# PogoFTDI.net
KiCad netlist of a schematic drawn in EAGLE
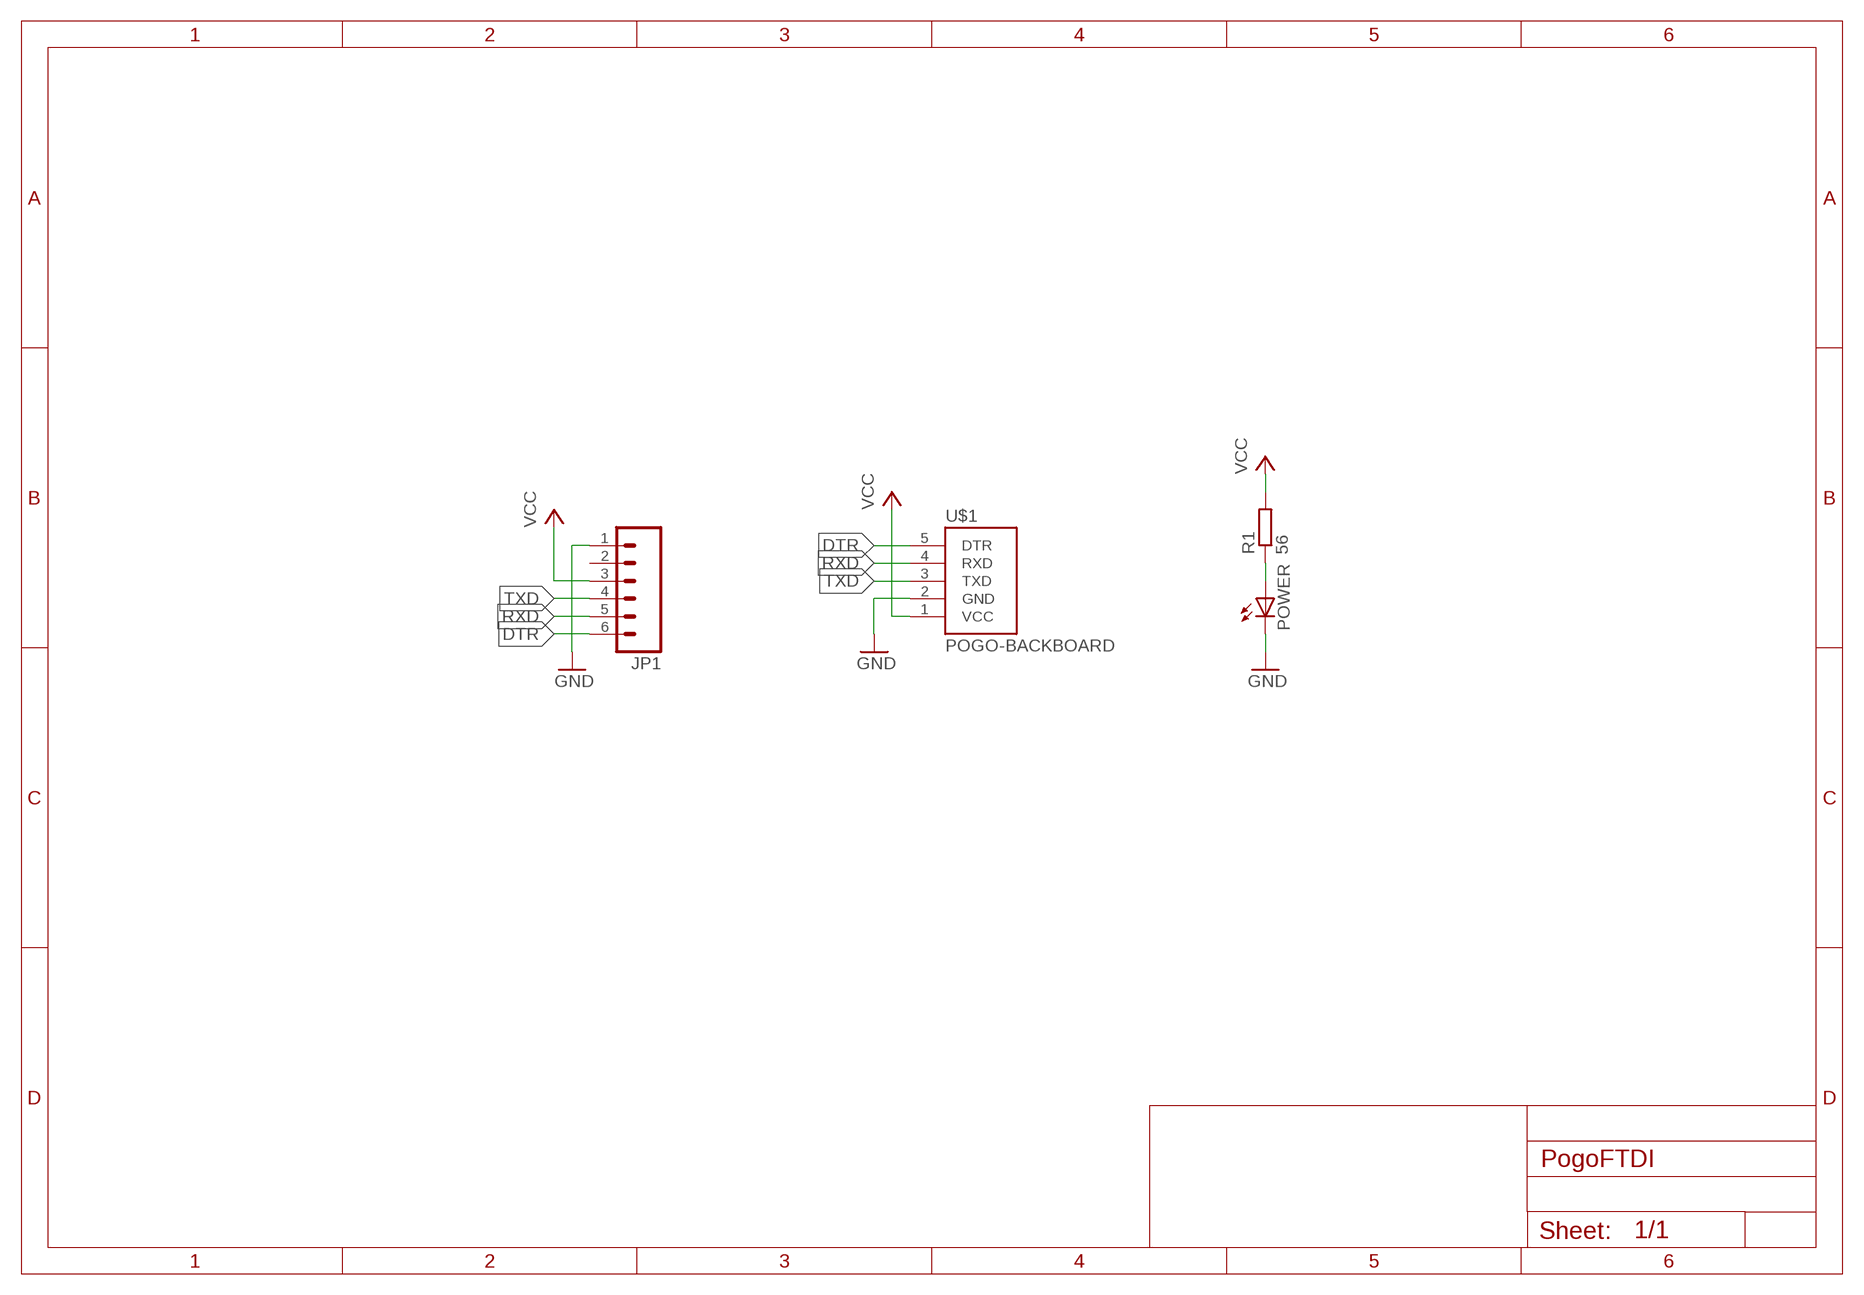
[diagram p0: schematic, sheet 1]

(export (version "E")
  (design (tool "Eeschema 10.0.6"))
  (components
    (comp (ref "JP1")
      (value "M06SIP")
      (footprint "eagle-import:1X06")
      (libsource (lib "eagle-import") (part "M06SIP"))
    )
    (comp (ref "POWER")
      (value "LEDCHIPLED_0603")
      (footprint "eagle-import:CHIPLED_0603")
      (libsource (lib "eagle-import") (part "LEDCHIPLED_0603"))
    )
    (comp (ref "R1")
      (value "56")
      (footprint "eagle-import:R0603")
      (libsource (lib "eagle-import") (part "R-EU_R0603"))
    )
    (comp (ref "U$1")
      (value "POGO-BACKBOARD")
      (footprint "eagle-import:POGO5-BACKMOUNT")
      (libsource (lib "eagle-import") (part "POGO-BACKBOARD"))
    )
  )
  (nets
    (net (code "1") (name "DTR") (class "Default")
      (node (ref "JP1") (pin "6") (pinfunction "6_6") (pintype "passive"))
      (node (ref "U$1") (pin "5") (pinfunction "DTR_5") (pintype "bidirectional"))
    )
    (net (code "2") (name "GND") (class "Default")
      (node (ref "JP1") (pin "1") (pinfunction "1_1") (pintype "passive"))
      (node (ref "POWER") (pin "C") (pinfunction "C_C") (pintype "passive"))
      (node (ref "U$1") (pin "2") (pinfunction "GND_2") (pintype "bidirectional"))
    )
    (net (code "3") (name "Net-(POWER-PadA)") (class "Default")
      (node (ref "POWER") (pin "A") (pinfunction "A_A") (pintype "passive"))
      (node (ref "R1") (pin "1") (pinfunction "1_1") (pintype "passive"))
    )
    (net (code "4") (name "RXD") (class "Default")
      (node (ref "JP1") (pin "5") (pinfunction "5_5") (pintype "passive"))
      (node (ref "U$1") (pin "4") (pinfunction "RXD_4") (pintype "bidirectional"))
    )
    (net (code "5") (name "TXD") (class "Default")
      (node (ref "JP1") (pin "4") (pinfunction "4_4") (pintype "passive"))
      (node (ref "U$1") (pin "3") (pinfunction "TXD_3") (pintype "bidirectional"))
    )
    (net (code "6") (name "VCC") (class "Default")
      (node (ref "JP1") (pin "3") (pinfunction "3_3") (pintype "passive"))
      (node (ref "R1") (pin "2") (pinfunction "2_2") (pintype "passive"))
      (node (ref "U$1") (pin "1") (pinfunction "VCC_1") (pintype "bidirectional"))
    )
    (net (code "7") (name "unconnected-(JP1-Pad2)") (class "Default")
      (node (ref "JP1") (pin "2") (pinfunction "2_2") (pintype "passive"))
    )
  )
)
